# Main.net
KiCad netlist of a schematic drawn in Altium Designer
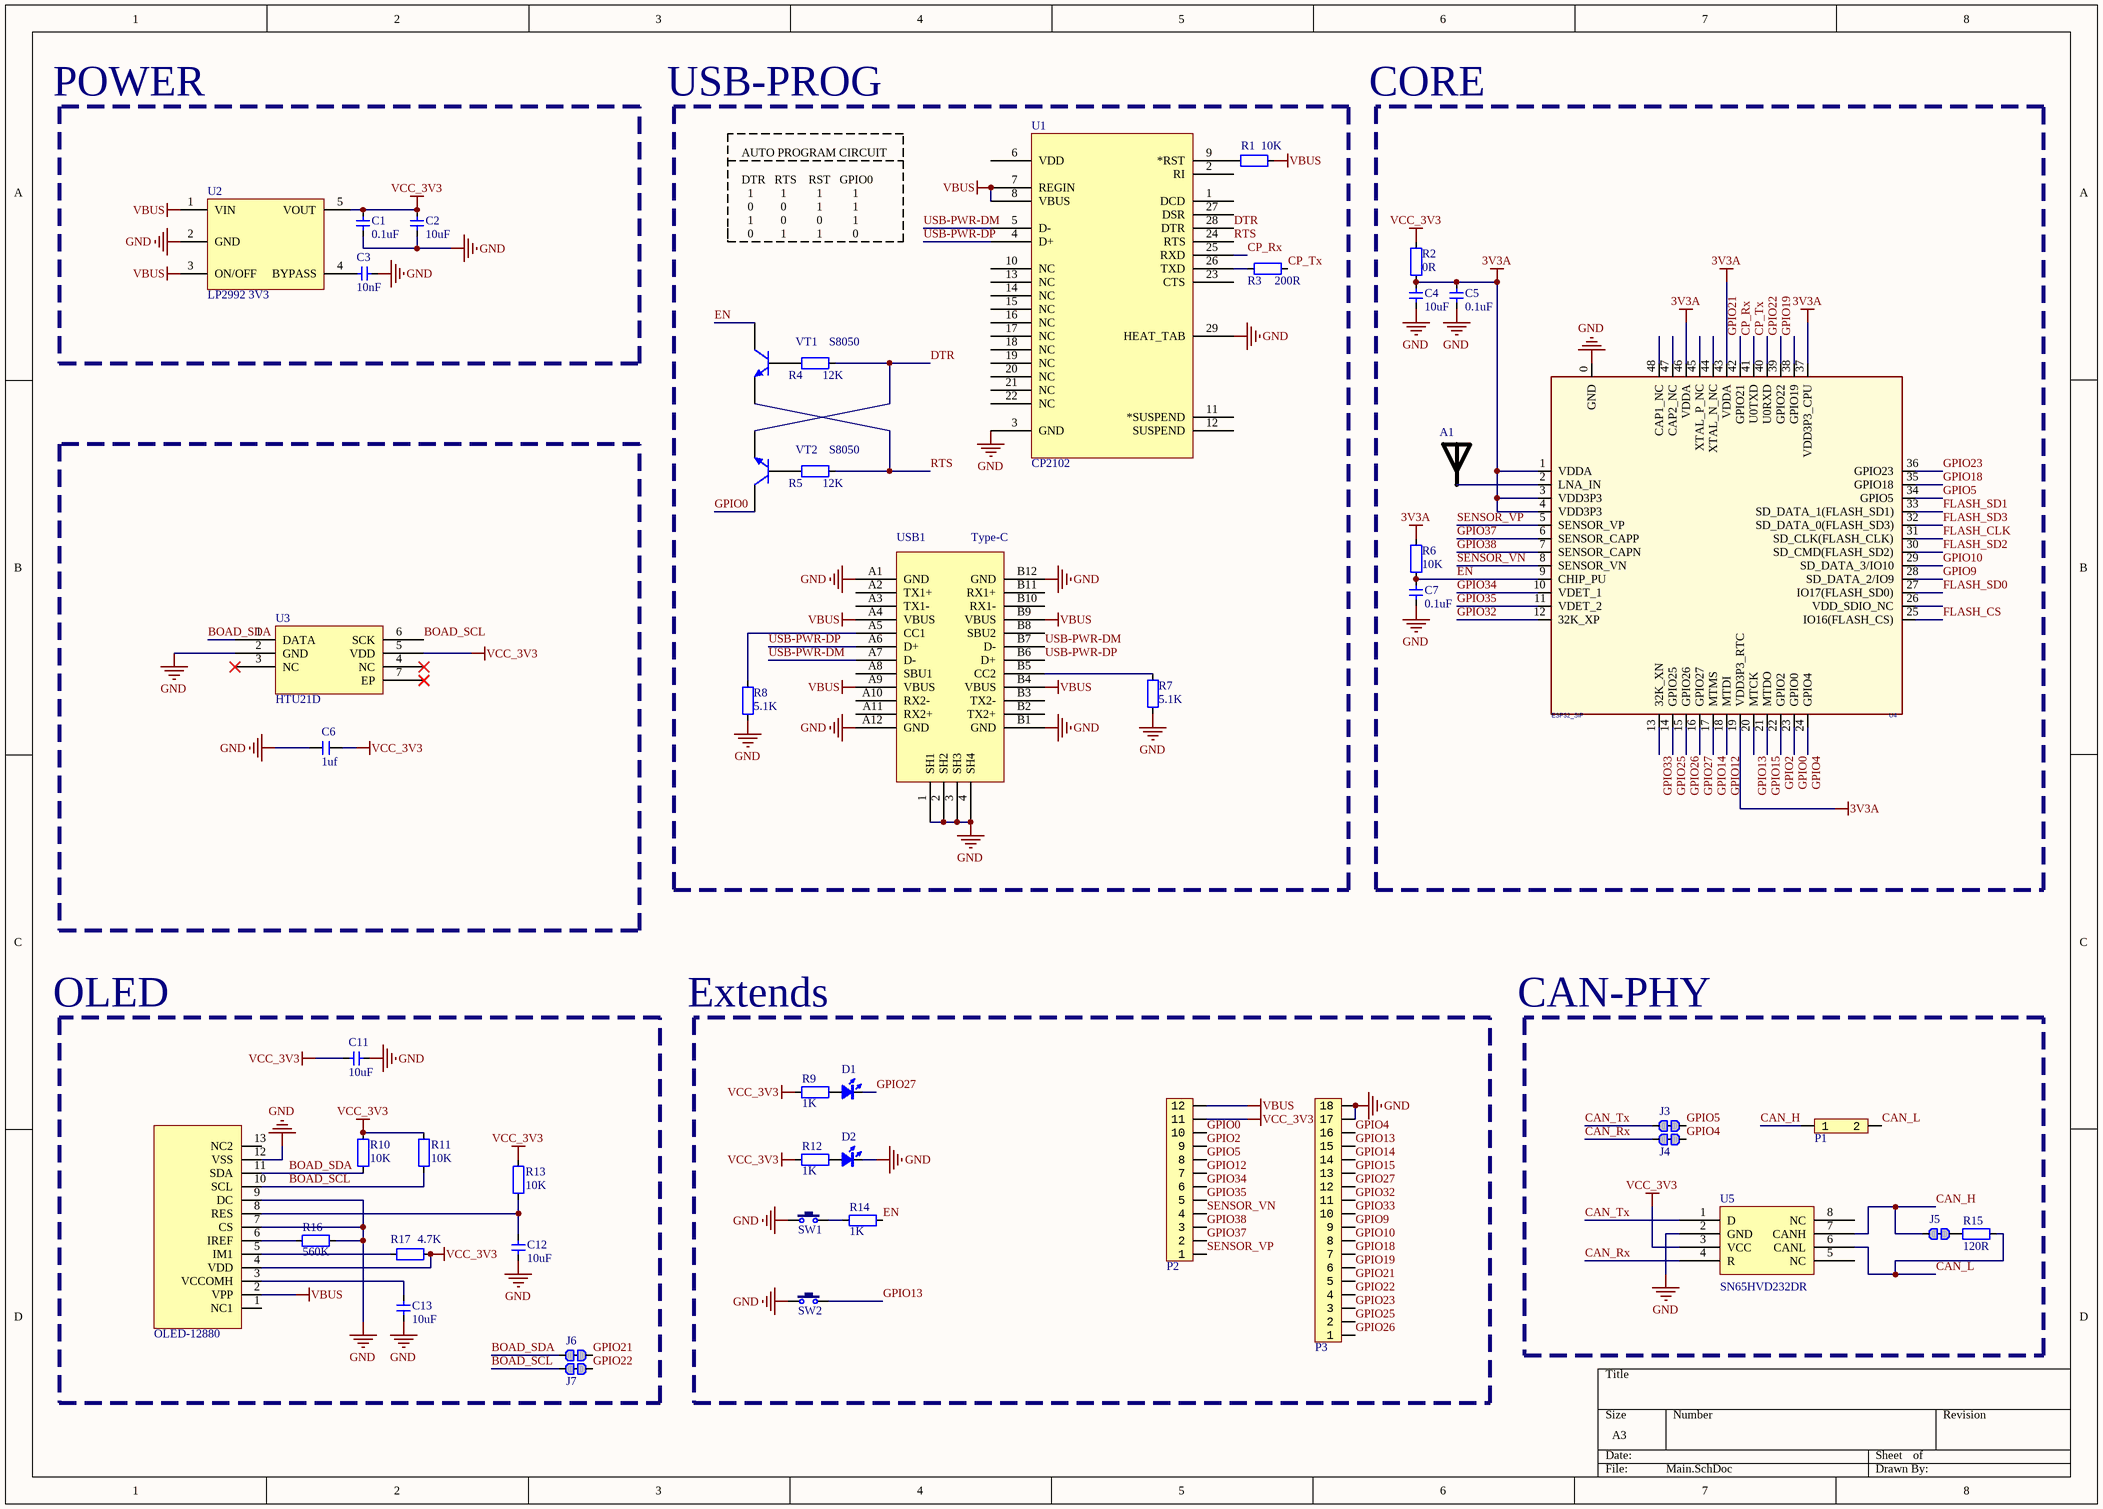
[diagram p0: Main.SchDoc]

(export (version "E")
  (design (tool "Eeschema 10.0.6"))
  (components
    (comp (ref "1")
      (value "OLED-12880")
      (footprint "OLED-12880")
      (libsource (lib "mLib") (part "OLED-12880"))
    )
    (comp (ref "A1")
      (value "RAINSUN")
      (footprint "ANT-Rainsun-AN5120")
      (libsource (lib "MyPcbLib") (part "ANT-Rainsun-AP5120"))
    )
    (comp (ref "C1")
      (value "0.1uF")
      (footprint "C 0402_L")
      (description "Capacitor")
      (libsource (lib "MyPcbLib") (part "电容-0402"))
    )
    (comp (ref "C2")
      (value "10uF")
      (footprint "C 0402_L")
      (description "Capacitor")
      (libsource (lib "MyPcbLib") (part "电容-0402"))
    )
    (comp (ref "C3")
      (value "10nF")
      (footprint "C 0402_L")
      (description "Capacitor")
      (libsource (lib "MyPcbLib") (part "电容-0402"))
    )
    (comp (ref "C4")
      (value "10uF")
      (footprint "C 0402_L")
      (description "Capacitor")
      (libsource (lib "MyPcbLib") (part "电容-0402"))
    )
    (comp (ref "C5")
      (value "0.1uF")
      (footprint "C 0402_L")
      (description "Capacitor")
      (libsource (lib "MyPcbLib") (part "电容-0402"))
    )
    (comp (ref "C6")
      (value "1uf")
      (footprint "C 0603_L")
      (description "无极性贴片电容")
      (fields (field (name "版权归属") "源创客"))
      (libsource (lib "3.1   - 电阻-电容-电感") (part "C"))
    )
    (comp (ref "C7")
      (value "0.1uF")
      (footprint "C 0402_L")
      (description "Capacitor")
      (libsource (lib "MyPcbLib") (part "电容-0402"))
    )
    (comp (ref "C11")
      (value "10uF")
      (footprint "C 0402_L")
      (description "Capacitor")
      (libsource (lib "MyPcbLib") (part "电容-0402"))
    )
    (comp (ref "C12")
      (value "10uF")
      (footprint "C 0402_L")
      (description "Capacitor")
      (libsource (lib "MyPcbLib") (part "电容-0402"))
    )
    (comp (ref "C13")
      (value "10uF")
      (footprint "C 0402_L")
      (description "Capacitor")
      (libsource (lib "MyPcbLib") (part "电容-0402"))
    )
    (comp (ref "D1")
      (value "color?")
      (footprint "LED_0402_RED")
      (description "LED")
      (libsource (lib "KitSprout") (part "LED_0402"))
    )
    (comp (ref "D2")
      (value "color?")
      (footprint "LED_0402_RED")
      (description "LED")
      (libsource (lib "KitSprout") (part "LED_0402"))
    )
    (comp (ref "J3")
      (value "跳线")
      (footprint "0402-0R")
      (description "Resistor")
      (fields (field (name "PUBLISHER") "Altium Limited"))
      (libsource (lib "MyPcbLib") (part "跳线"))
    )
    (comp (ref "J4")
      (value "跳线")
      (footprint "0402-0R")
      (description "Resistor")
      (fields (field (name "PUBLISHER") "Altium Limited"))
      (libsource (lib "MyPcbLib") (part "跳线"))
    )
    (comp (ref "J5")
      (value "跳线")
      (footprint "0402-0R")
      (description "Resistor")
      (fields (field (name "PUBLISHER") "Altium Limited"))
      (libsource (lib "MyPcbLib") (part "跳线"))
    )
    (comp (ref "J6")
      (value "跳线")
      (footprint "0402-0R")
      (description "Resistor")
      (fields (field (name "PUBLISHER") "Altium Limited"))
      (libsource (lib "MyPcbLib") (part "跳线"))
    )
    (comp (ref "J7")
      (value "跳线")
      (footprint "0402-0R")
      (description "Resistor")
      (fields (field (name "PUBLISHER") "Altium Limited"))
      (libsource (lib "MyPcbLib") (part "跳线"))
    )
    (comp (ref "P1")
      (value "HDR2x1_2.54")
      (footprint "HDR1X2_2.54_180")
      (description "Header")
      (libsource (lib "KitSprout") (part "HDR2x1_2.54"))
    )
    (comp (ref "P2")
      (value "HDR1x12_2.54")
      (footprint "HDR1X12_2.54_180")
      (description "Header")
      (libsource (lib "KitSprout") (part "HDR1x12_2.54"))
    )
    (comp (ref "P3")
      (value "HDR1x18_2.54")
      (footprint "HDR1X18_2.54_180")
      (description "Header")
      (libsource (lib "KitSprout") (part "HDR1x18_2.54"))
    )
    (comp (ref "R1")
      (value "10K")
      (footprint "R 0402_M")
      (description "Resistor")
      (libsource (lib "") (part "电阻-0402_3"))
    )
    (comp (ref "R2")
      (value "0R")
      (footprint "R 0402_M")
      (description "Resistor")
      (libsource (lib "") (part "电阻-0402_2"))
    )
    (comp (ref "R3")
      (value "200R")
      (footprint "R 0402_M")
      (description "Resistor")
      (libsource (lib "") (part "电阻-0402_3"))
    )
    (comp (ref "R4")
      (value "12K")
      (footprint "R 0402_M")
      (description "Resistor")
      (libsource (lib "") (part "电阻-0402_3"))
    )
    (comp (ref "R5")
      (value "12K")
      (footprint "R 0402_M")
      (description "Resistor")
      (libsource (lib "") (part "电阻-0402_3"))
    )
    (comp (ref "R6")
      (value "10K")
      (footprint "R 0402_M")
      (description "Resistor")
      (libsource (lib "") (part "电阻-0402_2"))
    )
    (comp (ref "R7")
      (value "5.1K")
      (footprint "R 0402_M")
      (description "Resistor")
      (libsource (lib "") (part "电阻-0402_2"))
    )
    (comp (ref "R8")
      (value "5.1K")
      (footprint "R 0402_M")
      (description "Resistor")
      (libsource (lib "") (part "电阻-0402_2"))
    )
    (comp (ref "R9")
      (value "1K")
      (footprint "R 0402_M")
      (description "Resistor")
      (libsource (lib "") (part "电阻-0402_1"))
    )
    (comp (ref "R10")
      (value "10K")
      (footprint "R 0402_M")
      (description "Resistor")
      (libsource (lib "MyPcbLib") (part "电阻-0402"))
    )
    (comp (ref "R11")
      (value "10K")
      (footprint "R 0402_M")
      (description "Resistor")
      (libsource (lib "MyPcbLib") (part "电阻-0402"))
    )
    (comp (ref "R12")
      (value "1K")
      (footprint "R 0402_M")
      (description "Resistor")
      (libsource (lib "") (part "电阻-0402_1"))
    )
    (comp (ref "R13")
      (value "10K")
      (footprint "R 0402_M")
      (description "Resistor")
      (libsource (lib "MyPcbLib") (part "电阻-0402"))
    )
    (comp (ref "R14")
      (value "1K")
      (footprint "R 0402_M")
      (description "Resistor")
      (libsource (lib "") (part "电阻-0402_1"))
    )
    (comp (ref "R15")
      (value "120R")
      (footprint "R 0402_M")
      (description "Resistor")
      (libsource (lib "") (part "电阻-0402_1"))
    )
    (comp (ref "R16")
      (value "560K")
      (footprint "R 0402_M")
      (description "Resistor")
      (libsource (lib "") (part "电阻-0402_1"))
    )
    (comp (ref "R17")
      (value "4.7K")
      (footprint "R 0402_M")
      (description "Resistor")
      (libsource (lib "") (part "电阻-0402_1"))
    )
    (comp (ref "SW1")
      (value "3x6x5")
      (footprint "SW-SMD_L4.0-W2.9-LS5.0")
      (description "3x6轻触开关")
      (fields (field (name "版权归属") "源创客"))
      (libsource (lib "5.1   - 按键-开关") (part "TSW 3x6"))
    )
    (comp (ref "SW2")
      (value "3x6x5")
      (footprint "SW-SMD_L4.0-W2.9-LS5.0")
      (description "3x6轻触开关")
      (fields (field (name "版权归属") "源创客"))
      (libsource (lib "5.1   - 按键-开关") (part "TSW 3x6"))
    )
    (comp (ref "U1")
      (value "CP2102")
      (footprint "QFN-28")
      (description "USB转TTL")
      (libsource (lib "mLib") (part "CP2102"))
    )
    (comp (ref "U2")
      (value "LP2992 3V3")
      (footprint "SOT23-5")
      (description "LDO")
      (libsource (lib "MyPcbLib") (part "LP2992"))
    )
    (comp (ref "U3")
      (value "HTU21D")
      (footprint "DFN-6_L3.0-W3.0-P1.00-BL-EP")
      (libsource (lib "HTU21D") (part "HTU21D"))
    )
    (comp (ref "U4")
      (value "ESP32_SIP")
      (footprint "QFN-48_7X7")
      (libsource (lib "MyPcbLib") (part "ESP32-PICO"))
    )
    (comp (ref "U5")
      (value "SN65HVD232D")
      (footprint "SO-8")
      (fields
        (field (name "MANUFACTURER") "Texas Instruments")
        (field (name "MANUFACTURER PART NUMBER") "SN65HVD232DR")
      )
      (libsource (lib "MyPcbLib") (part "SN65HVD232D"))
    )
    (comp (ref "USB1")
      (value "Type-C")
      (footprint "Type-C-TOP")
      (libsource (lib "MyPcbLib") (part "USB-Type-C-TOP"))
    )
    (comp (ref "VT1")
      (value "S8050")
      (footprint "SMT_TRIODE_NPN")
      (description "Surface mount NPN transistor, package SOT-23")
      (libsource (lib "MyPcbLib") (part "SMT_TRIODE_NPN"))
    )
    (comp (ref "VT2")
      (value "S8050")
      (footprint "SMT_TRIODE_NPN")
      (description "Surface mount NPN transistor, package SOT-23")
      (libsource (lib "MyPcbLib") (part "SMT_TRIODE_NPN"))
    )
  )
  (nets
    (net (code "1") (name "/BOAD_SCL") (class "Default")
      (node (ref "1") (pin "10") (pinfunction "SCL_10") (pintype "passive"))
      (node (ref "J7") (pin "1") (pinfunction "1_1") (pintype "passive"))
      (node (ref "R11") (pin "1") (pinfunction "1_1") (pintype "passive"))
      (node (ref "U3") (pin "6") (pinfunction "SCK_6") (pintype "passive"))
    )
    (net (code "2") (name "/BOAD_SDA") (class "Default")
      (node (ref "1") (pin "11") (pinfunction "SDA_11") (pintype "passive"))
      (node (ref "J6") (pin "1") (pinfunction "1_1") (pintype "passive"))
      (node (ref "R10") (pin "1") (pinfunction "1_1") (pintype "passive"))
      (node (ref "U3") (pin "1") (pinfunction "DATA_1") (pintype "passive"))
    )
    (net (code "3") (name "/CAN_H") (class "Default")
      (node (ref "J5") (pin "1") (pinfunction "1_1") (pintype "passive"))
      (node (ref "P1") (pin "1") (pinfunction "1_1") (pintype "passive"))
      (node (ref "U5") (pin "7") (pinfunction "CANH_7") (pintype "passive"))
    )
    (net (code "4") (name "/CAN_L") (class "Default")
      (node (ref "P1") (pin "2") (pinfunction "2_2") (pintype "passive"))
      (node (ref "R15") (pin "2") (pinfunction "2_2") (pintype "passive"))
      (node (ref "U5") (pin "6") (pinfunction "CANL_6") (pintype "passive"))
    )
    (net (code "5") (name "/CAN_Rx") (class "Default")
      (node (ref "J4") (pin "1") (pinfunction "1_1") (pintype "passive"))
      (node (ref "U5") (pin "4") (pinfunction "R_4") (pintype "passive"))
    )
    (net (code "6") (name "/CAN_Tx") (class "Default")
      (node (ref "J3") (pin "1") (pinfunction "1_1") (pintype "passive"))
      (node (ref "U5") (pin "1") (pinfunction "D_1") (pintype "passive"))
    )
    (net (code "7") (name "/CP_Rx") (class "Default")
      (node (ref "U1") (pin "25") (pinfunction "RXD_25") (pintype "passive"))
      (node (ref "U4") (pin "41") (pinfunction "U0TXD_41") (pintype "power_in"))
    )
    (net (code "8") (name "/CP_Tx") (class "Default")
      (node (ref "R3") (pin "1") (pinfunction "1_1") (pintype "passive"))
      (node (ref "U4") (pin "40") (pinfunction "U0RXD_40") (pintype "power_in"))
    )
    (net (code "9") (name "/DTR") (class "Default")
      (node (ref "R4") (pin "1") (pinfunction "1_1") (pintype "passive"))
      (node (ref "U1") (pin "28") (pinfunction "DTR_28") (pintype "passive"))
      (node (ref "VT2") (pin "2") (pinfunction "E_2") (pintype "passive"))
    )
    (net (code "10") (name "/EN") (class "Default")
      (node (ref "C7") (pin "1") (pinfunction "1_1") (pintype "passive"))
      (node (ref "R14") (pin "2") (pinfunction "2_2") (pintype "passive"))
      (node (ref "R6") (pin "2") (pinfunction "2_2") (pintype "passive"))
      (node (ref "U4") (pin "9") (pinfunction "CHIP_PU_9") (pintype "passive"))
      (node (ref "VT1") (pin "3") (pinfunction "C_3") (pintype "passive"))
    )
    (net (code "11") (name "/FLASH_CLK") (class "Default")
      (node (ref "U4") (pin "31") (pinfunction "SD_CLK(FLASH_CLK)_31") (pintype "passive"))
    )
    (net (code "12") (name "/FLASH_CS") (class "Default")
      (node (ref "U4") (pin "25") (pinfunction "IO16(FLASH_CS)_25") (pintype "passive"))
    )
    (net (code "13") (name "/FLASH_SD0") (class "Default")
      (node (ref "U4") (pin "27") (pinfunction "IO17(FLASH_SD0)_27") (pintype "passive"))
    )
    (net (code "14") (name "/FLASH_SD1") (class "Default")
      (node (ref "U4") (pin "33") (pinfunction "SD_DATA_1(FLASH_SD1)_33") (pintype "passive"))
    )
    (net (code "15") (name "/FLASH_SD2") (class "Default")
      (node (ref "U4") (pin "30") (pinfunction "SD_CMD(FLASH_SD2)_30") (pintype "passive"))
    )
    (net (code "16") (name "/FLASH_SD3") (class "Default")
      (node (ref "U4") (pin "32") (pinfunction "SD_DATA_0(FLASH_SD3)_32") (pintype "passive"))
    )
    (net (code "17") (name "/GPIO0") (class "Default")
      (node (ref "P2") (pin "10") (pinfunction "10_10") (pintype "passive"))
      (node (ref "U4") (pin "23") (pinfunction "GPIO0_23") (pintype "passive"))
      (node (ref "VT2") (pin "3") (pinfunction "C_3") (pintype "passive"))
    )
    (net (code "18") (name "/GPIO2") (class "Default")
      (node (ref "P2") (pin "9") (pinfunction "9_9") (pintype "passive"))
      (node (ref "U4") (pin "22") (pinfunction "GPIO2_22") (pintype "passive"))
    )
    (net (code "19") (name "/GPIO4") (class "Default")
      (node (ref "J4") (pin "2") (pinfunction "2_2") (pintype "passive"))
      (node (ref "P3") (pin "16") (pinfunction "16_16") (pintype "passive"))
      (node (ref "U4") (pin "24") (pinfunction "GPIO4_24") (pintype "passive"))
    )
    (net (code "20") (name "/GPIO5") (class "Default")
      (node (ref "J3") (pin "2") (pinfunction "2_2") (pintype "passive"))
      (node (ref "P2") (pin "8") (pinfunction "8_8") (pintype "passive"))
      (node (ref "U4") (pin "34") (pinfunction "GPIO5_34") (pintype "passive"))
    )
    (net (code "21") (name "/GPIO9") (class "Default")
      (node (ref "P3") (pin "9") (pinfunction "9_9") (pintype "passive"))
      (node (ref "U4") (pin "28") (pinfunction "SD_DATA_2/IO9_28") (pintype "passive"))
    )
    (net (code "22") (name "/GPIO10") (class "Default")
      (node (ref "P3") (pin "8") (pinfunction "8_8") (pintype "passive"))
      (node (ref "U4") (pin "29") (pinfunction "SD_DATA_3/IO10_29") (pintype "passive"))
    )
    (net (code "23") (name "/GPIO12") (class "Default")
      (node (ref "P2") (pin "7") (pinfunction "7_7") (pintype "passive"))
      (node (ref "U4") (pin "18") (pinfunction "MTDI_18") (pintype "passive"))
    )
    (net (code "24") (name "/GPIO13") (class "Default")
      (node (ref "P3") (pin "15") (pinfunction "15_15") (pintype "passive"))
      (node (ref "SW2") (pin "2") (pinfunction "2_2") (pintype "passive"))
      (node (ref "U4") (pin "20") (pinfunction "MTCK_20") (pintype "passive"))
    )
    (net (code "25") (name "/GPIO14") (class "Default")
      (node (ref "P3") (pin "14") (pinfunction "14_14") (pintype "passive"))
      (node (ref "U4") (pin "17") (pinfunction "MTMS_17") (pintype "passive"))
    )
    (net (code "26") (name "/GPIO15") (class "Default")
      (node (ref "P3") (pin "13") (pinfunction "13_13") (pintype "passive"))
      (node (ref "U4") (pin "21") (pinfunction "MTDO_21") (pintype "passive"))
    )
    (net (code "27") (name "/GPIO18") (class "Default")
      (node (ref "P3") (pin "7") (pinfunction "7_7") (pintype "passive"))
      (node (ref "U4") (pin "35") (pinfunction "GPIO18_35") (pintype "passive"))
    )
    (net (code "28") (name "/GPIO19") (class "Default")
      (node (ref "P3") (pin "6") (pinfunction "6_6") (pintype "passive"))
      (node (ref "U4") (pin "38") (pinfunction "GPIO19_38") (pintype "passive"))
    )
    (net (code "29") (name "/GPIO21") (class "Default")
      (node (ref "J6") (pin "2") (pinfunction "2_2") (pintype "passive"))
      (node (ref "P3") (pin "5") (pinfunction "5_5") (pintype "passive"))
      (node (ref "U4") (pin "42") (pinfunction "GPIO21_42") (pintype "passive"))
    )
    (net (code "30") (name "/GPIO22") (class "Default")
      (node (ref "J7") (pin "2") (pinfunction "2_2") (pintype "passive"))
      (node (ref "P3") (pin "4") (pinfunction "4_4") (pintype "passive"))
      (node (ref "U4") (pin "39") (pinfunction "GPIO22_39") (pintype "passive"))
    )
    (net (code "31") (name "/GPIO23") (class "Default")
      (node (ref "P3") (pin "3") (pinfunction "3_3") (pintype "passive"))
      (node (ref "U4") (pin "36") (pinfunction "GPIO23_36") (pintype "passive"))
    )
    (net (code "32") (name "/GPIO25") (class "Default")
      (node (ref "P3") (pin "2") (pinfunction "2_2") (pintype "passive"))
      (node (ref "U4") (pin "14") (pinfunction "GPIO25_14") (pintype "passive"))
    )
    (net (code "33") (name "/GPIO26") (class "Default")
      (node (ref "P3") (pin "1") (pinfunction "1_1") (pintype "passive"))
      (node (ref "U4") (pin "15") (pinfunction "GPIO26_15") (pintype "passive"))
    )
    (net (code "34") (name "/GPIO27") (class "Default")
      (node (ref "D1") (pin "2") (pinfunction "K_2") (pintype "passive"))
      (node (ref "P3") (pin "12") (pinfunction "12_12") (pintype "passive"))
      (node (ref "U4") (pin "16") (pinfunction "GPIO27_16") (pintype "passive"))
    )
    (net (code "35") (name "/GPIO32") (class "Default")
      (node (ref "P3") (pin "11") (pinfunction "11_11") (pintype "passive"))
      (node (ref "U4") (pin "12") (pinfunction "32K_XP_12") (pintype "passive"))
    )
    (net (code "36") (name "/GPIO33") (class "Default")
      (node (ref "P3") (pin "10") (pinfunction "10_10") (pintype "passive"))
      (node (ref "U4") (pin "13") (pinfunction "32K_XN_13") (pintype "passive"))
    )
    (net (code "37") (name "/GPIO34") (class "Default")
      (node (ref "P2") (pin "6") (pinfunction "6_6") (pintype "passive"))
      (node (ref "U4") (pin "10") (pinfunction "VDET_1_10") (pintype "passive"))
    )
    (net (code "38") (name "/GPIO35") (class "Default")
      (node (ref "P2") (pin "5") (pinfunction "5_5") (pintype "passive"))
      (node (ref "U4") (pin "11") (pinfunction "VDET_2_11") (pintype "passive"))
    )
    (net (code "39") (name "/GPIO37") (class "Default")
      (node (ref "P2") (pin "2") (pinfunction "2_2") (pintype "passive"))
      (node (ref "U4") (pin "6") (pinfunction "SENSOR_CAPP_6") (pintype "passive"))
    )
    (net (code "40") (name "/GPIO38") (class "Default")
      (node (ref "P2") (pin "3") (pinfunction "3_3") (pintype "passive"))
      (node (ref "U4") (pin "7") (pinfunction "SENSOR_CAPN_7") (pintype "passive"))
    )
    (net (code "41") (name "/RTS") (class "Default")
      (node (ref "R5") (pin "1") (pinfunction "1_1") (pintype "passive"))
      (node (ref "U1") (pin "24") (pinfunction "RTS_24") (pintype "passive"))
      (node (ref "VT1") (pin "2") (pinfunction "E_2") (pintype "passive"))
    )
    (net (code "42") (name "/SENSOR_VN") (class "Default")
      (node (ref "P2") (pin "4") (pinfunction "4_4") (pintype "passive"))
      (node (ref "U4") (pin "8") (pinfunction "SENSOR_VN_8") (pintype "passive"))
    )
    (net (code "43") (name "/SENSOR_VP") (class "Default")
      (node (ref "P2") (pin "1") (pinfunction "1_1") (pintype "passive"))
      (node (ref "U4") (pin "5") (pinfunction "SENSOR_VP_5") (pintype "passive"))
    )
    (net (code "44") (name "/USB-PWR-DM") (class "Default")
      (node (ref "U1") (pin "5") (pinfunction "D-_5") (pintype "passive"))
      (node (ref "USB1") (pin "A7") (pinfunction "D-_A7") (pintype "passive"))
      (node (ref "USB1") (pin "B7") (pinfunction "D-_B7") (pintype "passive"))
    )
    (net (code "45") (name "/USB-PWR-DP") (class "Default")
      (node (ref "U1") (pin "4") (pinfunction "D+_4") (pintype "passive"))
      (node (ref "USB1") (pin "A6") (pinfunction "D+_A6") (pintype "passive"))
      (node (ref "USB1") (pin "B6") (pinfunction "D+_B6") (pintype "passive"))
    )
    (net (code "46") (name "3V3A") (class "Default")
      (node (ref "C4") (pin "2") (pinfunction "2_2") (pintype "passive"))
      (node (ref "C5") (pin "2") (pinfunction "2_2") (pintype "passive"))
      (node (ref "R2") (pin "2") (pinfunction "2_2") (pintype "passive"))
      (node (ref "R6") (pin "1") (pinfunction "1_1") (pintype "passive"))
      (node (ref "U4") (pin "1") (pinfunction "VDDA_1") (pintype "power_in"))
      (node (ref "U4") (pin "19") (pinfunction "VDD3P3_RTC_19") (pintype "power_in"))
      (node (ref "U4") (pin "3") (pinfunction "VDD3P3_3") (pintype "power_in"))
      (node (ref "U4") (pin "37") (pinfunction "VDD3P3_CPU_37") (pintype "power_in"))
      (node (ref "U4") (pin "4") (pinfunction "VDD3P3_4") (pintype "power_in"))
      (node (ref "U4") (pin "43") (pinfunction "VDDA_43") (pintype "power_in"))
      (node (ref "U4") (pin "46") (pinfunction "VDDA_46") (pintype "power_in"))
    )
    (net (code "47") (name "GND") (class "Default")
      (node (ref "1") (pin "12") (pinfunction "VSS_12") (pintype "passive"))
      (node (ref "1") (pin "7") (pinfunction "CS_7") (pintype "passive"))
      (node (ref "1") (pin "9") (pinfunction "DC_9") (pintype "passive"))
      (node (ref "C1") (pin "1") (pinfunction "1_1") (pintype "passive"))
      (node (ref "C11") (pin "1") (pinfunction "1_1") (pintype "passive"))
      (node (ref "C12") (pin "1") (pinfunction "1_1") (pintype "passive"))
      (node (ref "C13") (pin "1") (pinfunction "1_1") (pintype "passive"))
      (node (ref "C2") (pin "1") (pinfunction "1_1") (pintype "passive"))
      (node (ref "C3") (pin "1") (pinfunction "1_1") (pintype "passive"))
      (node (ref "C4") (pin "1") (pinfunction "1_1") (pintype "passive"))
      (node (ref "C5") (pin "1") (pinfunction "1_1") (pintype "passive"))
      (node (ref "C6") (pin "1") (pinfunction "1_1") (pintype "passive"))
      (node (ref "C7") (pin "2") (pinfunction "2_2") (pintype "passive"))
      (node (ref "D2") (pin "2") (pinfunction "K_2") (pintype "passive"))
      (node (ref "P3") (pin "17") (pinfunction "17_17") (pintype "passive"))
      (node (ref "P3") (pin "18") (pinfunction "18_18") (pintype "passive"))
      (node (ref "R16") (pin "2") (pinfunction "2_2") (pintype "passive"))
      (node (ref "R7") (pin "2") (pinfunction "2_2") (pintype "passive"))
      (node (ref "R8") (pin "2") (pinfunction "2_2") (pintype "passive"))
      (node (ref "SW1") (pin "1") (pinfunction "1_1") (pintype "passive"))
      (node (ref "SW2") (pin "1") (pinfunction "1_1") (pintype "passive"))
      (node (ref "U1") (pin "29") (pinfunction "HEAT_TAB_29") (pintype "passive"))
      (node (ref "U1") (pin "3") (pinfunction "GND_3") (pintype "passive"))
      (node (ref "U2") (pin "2") (pinfunction "GND_2") (pintype "passive"))
      (node (ref "U3") (pin "2") (pinfunction "GND_2") (pintype "passive"))
      (node (ref "U4") (pin "0") (pinfunction "GND_0") (pintype "power_in"))
      (node (ref "U5") (pin "2") (pinfunction "GND_2") (pintype "passive"))
      (node (ref "USB1") (pin "1") (pinfunction "SH1_1") (pintype "passive"))
      (node (ref "USB1") (pin "2") (pinfunction "SH2_2") (pintype "passive"))
      (node (ref "USB1") (pin "3") (pinfunction "SH3_3") (pintype "passive"))
      (node (ref "USB1") (pin "4") (pinfunction "SH4_4") (pintype "passive"))
      (node (ref "USB1") (pin "A1") (pinfunction "GND_A1") (pintype "passive"))
      (node (ref "USB1") (pin "A12") (pinfunction "GND_A12") (pintype "passive"))
      (node (ref "USB1") (pin "B1") (pinfunction "GND_B1") (pintype "passive"))
      (node (ref "USB1") (pin "B12") (pinfunction "GND_B12") (pintype "passive"))
    )
    (net (code "48") (name "Net-(1-IM1)") (class "Default")
      (node (ref "1") (pin "5") (pinfunction "IM1_5") (pintype "passive"))
      (node (ref "R17") (pin "1") (pinfunction "1_1") (pintype "passive"))
    )
    (net (code "49") (name "Net-(1-IREF)") (class "Default")
      (node (ref "1") (pin "6") (pinfunction "IREF_6") (pintype "passive"))
      (node (ref "R16") (pin "1") (pinfunction "1_1") (pintype "passive"))
    )
    (net (code "50") (name "Net-(1-RES)") (class "Default")
      (node (ref "1") (pin "8") (pinfunction "RES_8") (pintype "passive"))
      (node (ref "C12") (pin "2") (pinfunction "2_2") (pintype "passive"))
      (node (ref "R13") (pin "1") (pinfunction "1_1") (pintype "passive"))
    )
    (net (code "51") (name "Net-(1-VCCOMH)") (class "Default")
      (node (ref "1") (pin "3") (pinfunction "VCCOMH_3") (pintype "passive"))
      (node (ref "C13") (pin "2") (pinfunction "2_2") (pintype "passive"))
    )
    (net (code "52") (name "Net-(D1-A)") (class "Default")
      (node (ref "D1") (pin "1") (pinfunction "A_1") (pintype "passive"))
      (node (ref "R9") (pin "2") (pinfunction "2_2") (pintype "passive"))
    )
    (net (code "53") (name "Net-(D2-A)") (class "Default")
      (node (ref "D2") (pin "1") (pinfunction "A_1") (pintype "passive"))
      (node (ref "R12") (pin "2") (pinfunction "2_2") (pintype "passive"))
    )
    (net (code "54") (name "Net-(J5-Pad2)") (class "Default")
      (node (ref "J5") (pin "2") (pinfunction "2_2") (pintype "passive"))
      (node (ref "R15") (pin "1") (pinfunction "1_1") (pintype "passive"))
    )
    (net (code "55") (name "Net-(R14-Pad1)") (class "Default")
      (node (ref "R14") (pin "1") (pinfunction "1_1") (pintype "passive"))
      (node (ref "SW1") (pin "2") (pinfunction "2_2") (pintype "passive"))
    )
    (net (code "56") (name "Net-(U1-*RST)") (class "Default")
      (node (ref "R1") (pin "2") (pinfunction "2_2") (pintype "passive"))
      (node (ref "U1") (pin "9") (pinfunction "*RST_9") (pintype "passive"))
    )
    (net (code "57") (name "Net-(U1-TXD)") (class "Default")
      (node (ref "R3") (pin "2") (pinfunction "2_2") (pintype "passive"))
      (node (ref "U1") (pin "26") (pinfunction "TXD_26") (pintype "passive"))
    )
    (net (code "58") (name "Net-(U2-BYPASS)") (class "Default")
      (node (ref "C3") (pin "2") (pinfunction "2_2") (pintype "passive"))
      (node (ref "U2") (pin "4") (pinfunction "BYPASS_4") (pintype "passive"))
    )
    (net (code "59") (name "Net-(U4-LNA_IN)") (class "Default")
      (node (ref "A1") (pin "1") (pinfunction "1_1") (pintype "passive"))
      (node (ref "U4") (pin "2") (pinfunction "LNA_IN_2") (pintype "passive"))
    )
    (net (code "60") (name "Net-(USB1-CC1)") (class "Default")
      (node (ref "R8") (pin "1") (pinfunction "1_1") (pintype "passive"))
      (node (ref "USB1") (pin "A5") (pinfunction "CC1_A5") (pintype "passive"))
    )
    (net (code "61") (name "Net-(USB1-CC2)") (class "Default")
      (node (ref "R7") (pin "1") (pinfunction "1_1") (pintype "passive"))
      (node (ref "USB1") (pin "B5") (pinfunction "CC2_B5") (pintype "passive"))
    )
    (net (code "62") (name "Net-(VT1-B)") (class "Default")
      (node (ref "R4") (pin "2") (pinfunction "2_2") (pintype "passive"))
      (node (ref "VT1") (pin "1") (pinfunction "B_1") (pintype "passive"))
    )
    (net (code "63") (name "Net-(VT2-B)") (class "Default")
      (node (ref "R5") (pin "2") (pinfunction "2_2") (pintype "passive"))
      (node (ref "VT2") (pin "1") (pinfunction "B_1") (pintype "passive"))
    )
    (net (code "64") (name "VBUS") (class "Default")
      (node (ref "1") (pin "2") (pinfunction "VPP_2") (pintype "passive"))
      (node (ref "P2") (pin "12") (pinfunction "12_12") (pintype "passive"))
      (node (ref "R1") (pin "1") (pinfunction "1_1") (pintype "passive"))
      (node (ref "U1") (pin "7") (pinfunction "REGIN_7") (pintype "passive"))
      (node (ref "U1") (pin "8") (pinfunction "VBUS_8") (pintype "passive"))
      (node (ref "U2") (pin "1") (pinfunction "VIN_1") (pintype "passive"))
      (node (ref "U2") (pin "3") (pinfunction "ON/OFF_3") (pintype "passive"))
      (node (ref "USB1") (pin "A4") (pinfunction "VBUS_A4") (pintype "passive"))
      (node (ref "USB1") (pin "A9") (pinfunction "VBUS_A9") (pintype "passive"))
      (node (ref "USB1") (pin "B4") (pinfunction "VBUS_B4") (pintype "passive"))
      (node (ref "USB1") (pin "B9") (pinfunction "VBUS_B9") (pintype "passive"))
    )
    (net (code "65") (name "VCC_3V3") (class "Default")
      (node (ref "1") (pin "4") (pinfunction "VDD_4") (pintype "passive"))
      (node (ref "C1") (pin "2") (pinfunction "2_2") (pintype "passive"))
      (node (ref "C11") (pin "2") (pinfunction "2_2") (pintype "passive"))
      (node (ref "C2") (pin "2") (pinfunction "2_2") (pintype "passive"))
      (node (ref "C6") (pin "2") (pinfunction "2_2") (pintype "passive"))
      (node (ref "P2") (pin "11") (pinfunction "11_11") (pintype "passive"))
      (node (ref "R10") (pin "2") (pinfunction "2_2") (pintype "passive"))
      (node (ref "R11") (pin "2") (pinfunction "2_2") (pintype "passive"))
      (node (ref "R12") (pin "1") (pinfunction "1_1") (pintype "passive"))
      (node (ref "R13") (pin "2") (pinfunction "2_2") (pintype "passive"))
      (node (ref "R17") (pin "2") (pinfunction "2_2") (pintype "passive"))
      (node (ref "R2") (pin "1") (pinfunction "1_1") (pintype "passive"))
      (node (ref "R9") (pin "1") (pinfunction "1_1") (pintype "passive"))
      (node (ref "U2") (pin "5") (pinfunction "VOUT_5") (pintype "passive"))
      (node (ref "U3") (pin "5") (pinfunction "VDD_5") (pintype "passive"))
      (node (ref "U5") (pin "3") (pinfunction "VCC_3") (pintype "passive"))
    )
    (net (code "66") (name "unconnected-(1-NC1-Pad1)") (class "Default")
      (node (ref "1") (pin "1") (pinfunction "NC1_1") (pintype "passive"))
    )
    (net (code "67") (name "unconnected-(1-NC2-Pad13)") (class "Default")
      (node (ref "1") (pin "13") (pinfunction "NC2_13") (pintype "passive"))
    )
    (net (code "68") (name "unconnected-(U1-*SUSPEND-Pad11)") (class "Default")
      (node (ref "U1") (pin "11") (pinfunction "*SUSPEND_11") (pintype "passive"))
    )
    (net (code "69") (name "unconnected-(U1-CTS-Pad23)") (class "Default")
      (node (ref "U1") (pin "23") (pinfunction "CTS_23") (pintype "passive"))
    )
    (net (code "70") (name "unconnected-(U1-DCD-Pad1)") (class "Default")
      (node (ref "U1") (pin "1") (pinfunction "DCD_1") (pintype "passive"))
    )
    (net (code "71") (name "unconnected-(U1-DSR-Pad27)") (class "Default")
      (node (ref "U1") (pin "27") (pinfunction "DSR_27") (pintype "passive"))
    )
    (net (code "72") (name "unconnected-(U1-NC-Pad10)") (class "Default")
      (node (ref "U1") (pin "10") (pinfunction "NC_10") (pintype "passive"))
    )
    (net (code "73") (name "unconnected-(U1-NC-Pad13)") (class "Default")
      (node (ref "U1") (pin "13") (pinfunction "NC_13") (pintype "passive"))
    )
    (net (code "74") (name "unconnected-(U1-NC-Pad14)") (class "Default")
      (node (ref "U1") (pin "14") (pinfunction "NC_14") (pintype "passive"))
    )
    (net (code "75") (name "unconnected-(U1-NC-Pad15)") (class "Default")
      (node (ref "U1") (pin "15") (pinfunction "NC_15") (pintype "passive"))
    )
    (net (code "76") (name "unconnected-(U1-NC-Pad16)") (class "Default")
      (node (ref "U1") (pin "16") (pinfunction "NC_16") (pintype "passive"))
    )
    (net (code "77") (name "unconnected-(U1-NC-Pad17)") (class "Default")
      (node (ref "U1") (pin "17") (pinfunction "NC_17") (pintype "passive"))
    )
    (net (code "78") (name "unconnected-(U1-NC-Pad18)") (class "Default")
      (node (ref "U1") (pin "18") (pinfunction "NC_18") (pintype "passive"))
    )
    (net (code "79") (name "unconnected-(U1-NC-Pad19)") (class "Default")
      (node (ref "U1") (pin "19") (pinfunction "NC_19") (pintype "passive"))
    )
    (net (code "80") (name "unconnected-(U1-NC-Pad20)") (class "Default")
      (node (ref "U1") (pin "20") (pinfunction "NC_20") (pintype "passive"))
    )
    (net (code "81") (name "unconnected-(U1-NC-Pad21)") (class "Default")
      (node (ref "U1") (pin "21") (pinfunction "NC_21") (pintype "passive"))
    )
    (net (code "82") (name "unconnected-(U1-NC-Pad22)") (class "Default")
      (node (ref "U1") (pin "22") (pinfunction "NC_22") (pintype "passive"))
    )
    (net (code "83") (name "unconnected-(U1-RI-Pad2)") (class "Default")
      (node (ref "U1") (pin "2") (pinfunction "RI_2") (pintype "passive"))
    )
    (net (code "84") (name "unconnected-(U1-SUSPEND-Pad12)") (class "Default")
      (node (ref "U1") (pin "12") (pinfunction "SUSPEND_12") (pintype "passive"))
    )
    (net (code "85") (name "unconnected-(U1-VDD-Pad6)") (class "Default")
      (node (ref "U1") (pin "6") (pinfunction "VDD_6") (pintype "passive"))
    )
    (net (code "86") (name "unconnected-(U3-EP-Pad7)") (class "Default")
      (node (ref "U3") (pin "7") (pinfunction "EP_7") (pintype "passive+no_connect"))
    )
    (net (code "87") (name "unconnected-(U3-NC-Pad3)") (class "Default")
      (node (ref "U3") (pin "3") (pinfunction "NC_3") (pintype "passive+no_connect"))
    )
    (net (code "88") (name "unconnected-(U3-NC-Pad4)") (class "Default")
      (node (ref "U3") (pin "4") (pinfunction "NC_4") (pintype "passive+no_connect"))
    )
    (net (code "89") (name "unconnected-(U4-CAP1_NC-Pad48)") (class "Default")
      (node (ref "U4") (pin "48") (pinfunction "CAP1_NC_48") (pintype "passive"))
    )
    (net (code "90") (name "unconnected-(U4-CAP2_NC-Pad47)") (class "Default")
      (node (ref "U4") (pin "47") (pinfunction "CAP2_NC_47") (pintype "passive"))
    )
    (net (code "91") (name "unconnected-(U4-VDD_SDIO_NC-Pad26)") (class "Default")
      (node (ref "U4") (pin "26") (pinfunction "VDD_SDIO_NC_26") (pintype "passive"))
    )
    (net (code "92") (name "unconnected-(U4-XTAL_N_NC-Pad44)") (class "Default")
      (node (ref "U4") (pin "44") (pinfunction "XTAL_N_NC_44") (pintype "passive"))
    )
    (net (code "93") (name "unconnected-(U4-XTAL_P_NC-Pad45)") (class "Default")
      (node (ref "U4") (pin "45") (pinfunction "XTAL_P_NC_45") (pintype "passive"))
    )
    (net (code "94") (name "unconnected-(U5-NC-Pad5)") (class "Default")
      (node (ref "U5") (pin "5") (pinfunction "NC_5") (pintype "passive"))
    )
    (net (code "95") (name "unconnected-(U5-NC-Pad8)") (class "Default")
      (node (ref "U5") (pin "8") (pinfunction "NC_8") (pintype "passive"))
    )
    (net (code "96") (name "unconnected-(USB1-RX1+-PadB11)") (class "Default")
      (node (ref "USB1") (pin "B11") (pinfunction "RX1+_B11") (pintype "passive"))
    )
    (net (code "97") (name "unconnected-(USB1-RX1--PadB10)") (class "Default")
      (node (ref "USB1") (pin "B10") (pinfunction "RX1-_B10") (pintype "passive"))
    )
    (net (code "98") (name "unconnected-(USB1-RX2+-PadA11)") (class "Default")
      (node (ref "USB1") (pin "A11") (pinfunction "RX2+_A11") (pintype "passive"))
    )
    (net (code "99") (name "unconnected-(USB1-RX2--PadA10)") (class "Default")
      (node (ref "USB1") (pin "A10") (pinfunction "RX2-_A10") (pintype "passive"))
    )
    (net (code "100") (name "unconnected-(USB1-SBU1-PadA8)") (class "Default")
      (node (ref "USB1") (pin "A8") (pinfunction "SBU1_A8") (pintype "passive"))
    )
    (net (code "101") (name "unconnected-(USB1-SBU2-PadB8)") (class "Default")
      (node (ref "USB1") (pin "B8") (pinfunction "SBU2_B8") (pintype "passive"))
    )
    (net (code "102") (name "unconnected-(USB1-TX1+-PadA2)") (class "Default")
      (node (ref "USB1") (pin "A2") (pinfunction "TX1+_A2") (pintype "passive"))
    )
    (net (code "103") (name "unconnected-(USB1-TX1--PadA3)") (class "Default")
      (node (ref "USB1") (pin "A3") (pinfunction "TX1-_A3") (pintype "passive"))
    )
    (net (code "104") (name "unconnected-(USB1-TX2+-PadB2)") (class "Default")
      (node (ref "USB1") (pin "B2") (pinfunction "TX2+_B2") (pintype "passive"))
    )
    (net (code "105") (name "unconnected-(USB1-TX2--PadB3)") (class "Default")
      (node (ref "USB1") (pin "B3") (pinfunction "TX2-_B3") (pintype "passive"))
    )
  )
)
